# Nevron_v4.net
KiCad netlist of a schematic drawn in Altium Designer
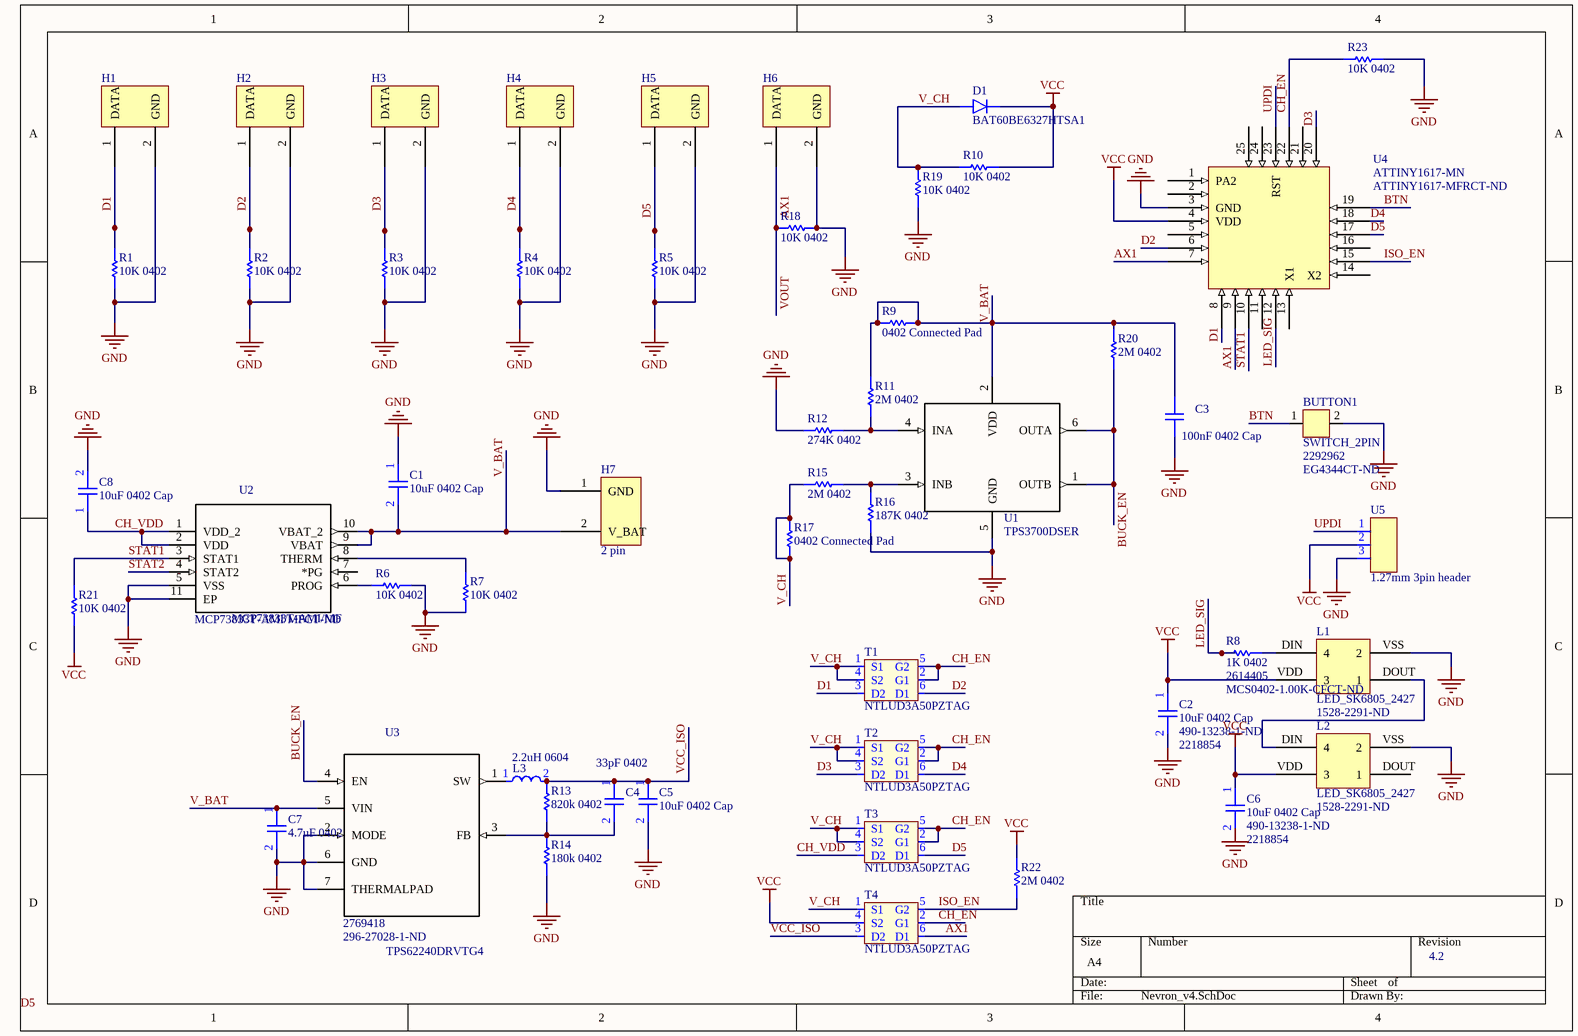
[diagram p0: Nevron_v4.SchDoc]

(export (version "E")
  (design (tool "Eeschema 10.0.6"))
  (components
    (comp (ref "BUTTON1")
      (value "SWITCH_2PIN")
      (footprint "SWITCH- TL1015AF160QG")
      (fields
        (field (name "SUPPLIER PART NUMBER 1") "2292962")
        (field (name "SUPPLIER PART NUMBER 2") "EG4344CT-ND")
      )
      (libsource (lib "Nevron_v4") (part "SWITCH_2PIN"))
    )
    (comp (ref "C1")
      (value "10uF 0402 Cap")
      (footprint "0402 Cap")
      (libsource (lib "Nevron_v4") (part "10uF 0402 Cap"))
    )
    (comp (ref "C2")
      (value "10uF 0402 Cap")
      (footprint "0402 Cap")
      (fields
        (field (name "SUPPLIER PART NUMBER 1") "490-13238-1-ND")
        (field (name "SUPPLIER PART NUMBER 2") "2218854")
      )
      (libsource (lib "Nevron_v4") (part "10uF 0402 Cap"))
    )
    (comp (ref "C3")
      (value "100nF 0402 Cap")
      (footprint "0402 Cap")
      (libsource (lib "Nevron_v4") (part "100nF 0402 Cap"))
    )
    (comp (ref "C4")
      (value "33pF 0402")
      (footprint "0402 Cap")
      (libsource (lib "Nevron_v4") (part "33pF 0402"))
    )
    (comp (ref "C5")
      (value "10uF 0402 Cap")
      (footprint "0402 Cap")
      (libsource (lib "Nevron_v4") (part "10uF 0402 Cap"))
    )
    (comp (ref "C6")
      (value "10uF 0402 Cap")
      (footprint "0402 Cap")
      (fields
        (field (name "SUPPLIER PART NUMBER 1") "490-13238-1-ND")
        (field (name "SUPPLIER PART NUMBER 2") "2218854")
      )
      (libsource (lib "Nevron_v4") (part "10uF 0402 Cap"))
    )
    (comp (ref "C7")
      (value "4.7uF 0402")
      (footprint "0402 Cap")
      (libsource (lib "Nevron_v4") (part "4.7uF 0402"))
    )
    (comp (ref "C8")
      (value "10uF 0402 Cap")
      (footprint "0402 Cap")
      (libsource (lib "Nevron_v4") (part "10uF 0402 Cap"))
    )
    (comp (ref "D1")
      (value "BAT60BE6327HTSA1")
      (footprint "BAT60BE6327HTSA1")
      (description "Diode Schottky 10V 3A Automotive 2-Pin SOD-323 T/R")
      (fields (field (name "MANUFACTURER") "Infineon"))
      (libsource (lib "Nevron_v4") (part "BAT60BE6327HTSA1"))
    )
    (comp (ref "H1")
      (value "Magnetci con. 2 pin")
      (footprint "Magnetic con. 2 pin")
      (libsource (lib "Nevron_v4") (part "Magnetci con. 2 pin"))
    )
    (comp (ref "H2")
      (value "Magnetci con. 2 pin")
      (footprint "Magnetic con. 2 pin")
      (libsource (lib "Nevron_v4") (part "Magnetci con. 2 pin"))
    )
    (comp (ref "H3")
      (value "Magnetci con. 2 pin")
      (footprint "Magnetic con. 2 pin")
      (libsource (lib "Nevron_v4") (part "Magnetci con. 2 pin"))
    )
    (comp (ref "H4")
      (value "Magnetci con. 2 pin")
      (footprint "Magnetic con. 2 pin")
      (libsource (lib "Nevron_v4") (part "Magnetci con. 2 pin"))
    )
    (comp (ref "H5")
      (value "Magnetci con. 2 pin")
      (footprint "Magnetic con. 2 pin")
      (libsource (lib "Nevron_v4") (part "Magnetci con. 2 pin"))
    )
    (comp (ref "H6")
      (value "Magnetci con. 2 pin")
      (footprint "Magnetic con. 2 pin")
      (libsource (lib "Nevron_v4") (part "Magnetci con. 2 pin"))
    )
    (comp (ref "H7") (value "2 pin") (footprint "2_PIN") (libsource (lib "Nevron_v1") (part "2 pin")))
    (comp (ref "L1")
      (value "LED_SK6805_2427")
      (footprint "LED_SK6805_2427")
      (fields (field (name "SUPPLIER PART NUMBER 1") "1528-2291-ND"))
      (libsource (lib "Nevron_v4") (part "LED_SK6805_2427"))
    )
    (comp (ref "L2")
      (value "LED_SK6805_2427")
      (footprint "LED_SK6805_2427")
      (fields (field (name "SUPPLIER PART NUMBER 1") "1528-2291-ND"))
      (libsource (lib "Nevron_v4") (part "LED_SK6805_2427"))
    )
    (comp (ref "L3")
      (value "2.2uH 0604")
      (footprint "0603 inductor")
      (libsource (lib "Nevron_v4") (part "2.2uH 0604"))
    )
    (comp (ref "R1")
      (value "10K 0402")
      (footprint "0402 Res")
      (libsource (lib "Nevron_v4") (part "10K 0402"))
    )
    (comp (ref "R2")
      (value "10K 0402")
      (footprint "0402 Res")
      (libsource (lib "Nevron_v4") (part "10K 0402"))
    )
    (comp (ref "R3")
      (value "10K 0402")
      (footprint "0402 Res")
      (libsource (lib "Nevron_v4") (part "10K 0402"))
    )
    (comp (ref "R4")
      (value "10K 0402")
      (footprint "0402 Res")
      (libsource (lib "Nevron_v4") (part "10K 0402"))
    )
    (comp (ref "R5")
      (value "10K 0402")
      (footprint "0402 Res")
      (libsource (lib "Nevron_v4") (part "10K 0402"))
    )
    (comp (ref "R6")
      (value "10K 0402")
      (footprint "0402 Res")
      (libsource (lib "Nevron_v4") (part "10K 0402"))
    )
    (comp (ref "R7")
      (value "10K 0402")
      (footprint "0402 Res")
      (libsource (lib "Nevron_v4") (part "10K 0402"))
    )
    (comp (ref "R8")
      (value "1K 0402")
      (footprint "0402 Res")
      (fields
        (field (name "SUPPLIER PART NUMBER 1") "2614405")
        (field (name "SUPPLIER PART NUMBER 2") "MCS0402-1.00K-CFCT-ND")
      )
      (libsource (lib "Nevron_v4") (part "1K 0402"))
    )
    (comp (ref "R9")
      (value "0402 Connected Pad")
      (footprint "0402 connected pad")
      (libsource (lib "Nevron_v4") (part "0402 Connected Pad"))
    )
    (comp (ref "R10")
      (value "10K 0402")
      (footprint "0402 Res")
      (libsource (lib "Nevron_v4") (part "10K 0402"))
    )
    (comp (ref "R11")
      (value "2M 0402")
      (footprint "0402 Res")
      (description "RES SMD 2M OHM 1% 1/16W 0402")
      (fields
        (field (name "MANUFACTURER") "Vishay Dale")
        (field (name "MANUFACTURER PART NUMBER") "CRCW04021M00DHEDP")
      )
      (libsource (lib "Nevron_v4") (part "2M 0402"))
    )
    (comp (ref "R12")
      (value "274K 0402")
      (footprint "0402 Res")
      (libsource (lib "Nevron_v4") (part "274K 0402"))
    )
    (comp (ref "R13")
      (value "820k 0402")
      (footprint "0402 Res")
      (libsource (lib "Nevron_v4") (part "820k 0402"))
    )
    (comp (ref "R14")
      (value "180k 0402")
      (footprint "0402 Res")
      (libsource (lib "Nevron_v4") (part "180k 0402"))
    )
    (comp (ref "R15")
      (value "2M 0402")
      (footprint "0402 Res")
      (description "RES SMD 2M OHM 1% 1/16W 0402")
      (fields
        (field (name "MANUFACTURER") "Vishay Dale")
        (field (name "MANUFACTURER PART NUMBER") "CRCW04021M00DHEDP")
      )
      (libsource (lib "Nevron_v4") (part "2M 0402"))
    )
    (comp (ref "R16")
      (value "187K 0402")
      (footprint "0402 Res")
      (libsource (lib "Nevron_v4") (part "187K 0402"))
    )
    (comp (ref "R17")
      (value "0402 Connected Pad")
      (footprint "0402 connected pad")
      (libsource (lib "Nevron_v4") (part "0402 Connected Pad"))
    )
    (comp (ref "R18")
      (value "10K 0402")
      (footprint "0402 Res")
      (libsource (lib "Nevron_v4") (part "10K 0402"))
    )
    (comp (ref "R19")
      (value "10K 0402")
      (footprint "0402 Res")
      (libsource (lib "Nevron_v4") (part "10K 0402"))
    )
    (comp (ref "R20")
      (value "2M 0402")
      (footprint "0402 Res")
      (description "RES SMD 2M OHM 1% 1/16W 0402")
      (fields
        (field (name "MANUFACTURER") "Vishay Dale")
        (field (name "MANUFACTURER PART NUMBER") "CRCW04021M00DHEDP")
      )
      (libsource (lib "Nevron_v4") (part "2M 0402"))
    )
    (comp (ref "R21")
      (value "10K 0402")
      (footprint "0402 Res")
      (libsource (lib "Nevron_v4") (part "10K 0402"))
    )
    (comp (ref "R22")
      (value "2M 0402")
      (footprint "0402 Res")
      (description "RES SMD 2M OHM 1% 1/16W 0402")
      (fields
        (field (name "MANUFACTURER") "Vishay Dale")
        (field (name "MANUFACTURER PART NUMBER") "CRCW04021M00DHEDP")
      )
      (libsource (lib "Nevron_v4") (part "2M 0402"))
    )
    (comp (ref "R23")
      (value "10K 0402")
      (footprint "0402 Res")
      (libsource (lib "Nevron_v4") (part "10K 0402"))
    )
    (comp (ref "T1")
      (value "NTLUD3A50PZTAG")
      (footprint "NTLUD3A50PZTAG")
      (libsource (lib "Nevron_v4") (part "NTLUD3A50PZTAG"))
    )
    (comp (ref "T2")
      (value "NTLUD3A50PZTAG")
      (footprint "NTLUD3A50PZTAG")
      (libsource (lib "Nevron_v4") (part "NTLUD3A50PZTAG"))
    )
    (comp (ref "T3")
      (value "NTLUD3A50PZTAG")
      (footprint "NTLUD3A50PZTAG")
      (libsource (lib "Nevron_v4") (part "NTLUD3A50PZTAG"))
    )
    (comp (ref "T4")
      (value "NTLUD3A50PZTAG")
      (footprint "NTLUD3A50PZTAG")
      (libsource (lib "Nevron_v4") (part "NTLUD3A50PZTAG"))
    )
    (comp (ref "U1")
      (value "TPS3700DSER")
      (footprint "TPS3700DSER")
      (description "IC COMPARATOR WINDOW")
      (fields (field (name "MANUFACTURER") "Texas Instruments"))
      (libsource (lib "Nevron_v4") (part "TPS3700DSER"))
    )
    (comp (ref "U2")
      (value "MCP73833T-AMI/MF")
      (footprint "MCP73833T-AMI/MF")
      (description "Linear Charge Management Controller Li-Ion/Li-Pol 1mA 4.2V/4.35V/4.4V/4.5V 10-Pin DFN EP T/R")
      (fields
        (field (name "MP") "MCP73833-AMI/UN")
        (field (name "MF") "Microchip")
        (field (name "SUPPLIER PART NUMBER 1") "MCP73833T-AMI/MFCT-ND")
      )
      (libsource (lib "Nevron_v4") (part "MCP73833T-AMI/MF"))
    )
    (comp (ref "U3")
      (value "TPS62240DRVTG4")
      (footprint "TPS62240DRVR")
      (description "Conv DC-DC 2V to 6V Synchronous Step Down Single-Out 0.6V to 6V 0.3A 6-Pin WSON EP T/R")
      (fields
        (field (name "MF") "Texas Instruments")
        (field (name "SUPPLIER PART NUMBER 1") "2769418")
        (field (name "SUPPLIER PART NUMBER 2") "296-27028-1-ND")
      )
      (libsource (lib "Nevron_v4") (part "TPS62240DRVR"))
    )
    (comp (ref "U4")
      (value "ATTINY1617-MN")
      (footprint "ATtiny1617_QFN50P400X400X90_HS-25M")
      (fields (field (name "SUPPLIER PART NUMBER 1") "ATTINY1617-MFRCT-ND"))
      (libsource (lib "Nevron_v4") (part "ATTINY1617-MN"))
    )
    (comp (ref "U5")
      (value "1.27mm 3pin header")
      (footprint "1.27mm 3pin header")
      (libsource (lib "Nevron_v4") (part "1.27mm 3pin header"))
    )
  )
  (nets
    (net (code "1") (name "/AX1") (class "Default")
      (node (ref "H6") (pin "1") (pinfunction "DATA_1") (pintype "passive"))
      (node (ref "R18") (pin "1") (pintype "passive"))
      (node (ref "T4") (pin "6") (pinfunction "D1_6") (pintype "passive"))
      (node (ref "U4") (pin "7") (pintype "input"))
      (node (ref "U4") (pin "9") (pintype "input"))
    )
    (net (code "2") (name "/BTN") (class "Default")
      (node (ref "BUTTON1") (pin "1") (pintype "passive"))
      (node (ref "U4") (pin "19") (pintype "input"))
    )
    (net (code "3") (name "/BUCK_EN") (class "Default")
      (node (ref "R20") (pin "2") (pintype "passive"))
      (node (ref "U1") (pin "1") (pinfunction "OUTB_1") (pintype "output"))
      (node (ref "U1") (pin "6") (pinfunction "OUTA_6") (pintype "output"))
      (node (ref "U3") (pin "4") (pinfunction "EN_4") (pintype "input"))
    )
    (net (code "4") (name "/CH_EN") (class "Default")
      (node (ref "R23") (pin "1") (pintype "passive"))
      (node (ref "T1") (pin "2") (pinfunction "G1_2") (pintype "passive"))
      (node (ref "T1") (pin "5") (pinfunction "G2_5") (pintype "passive"))
      (node (ref "T2") (pin "2") (pinfunction "G1_2") (pintype "passive"))
      (node (ref "T2") (pin "5") (pinfunction "G2_5") (pintype "passive"))
      (node (ref "T3") (pin "2") (pinfunction "G1_2") (pintype "passive"))
      (node (ref "T3") (pin "5") (pinfunction "G2_5") (pintype "passive"))
      (node (ref "T4") (pin "2") (pinfunction "G1_2") (pintype "passive"))
      (node (ref "U4") (pin "22") (pintype "input"))
    )
    (net (code "5") (name "/CH_VDD") (class "Default")
      (node (ref "C8") (pin "1") (pintype "passive"))
      (node (ref "T3") (pin "3") (pinfunction "D2_3") (pintype "passive"))
      (node (ref "U2") (pin "1") (pinfunction "VDD_2_1") (pintype "power_in"))
      (node (ref "U2") (pin "2") (pinfunction "VDD_2") (pintype "power_in"))
    )
    (net (code "6") (name "/D1") (class "Default")
      (node (ref "H1") (pin "1") (pinfunction "DATA_1") (pintype "passive"))
      (node (ref "R1") (pin "1") (pintype "passive"))
      (node (ref "T1") (pin "3") (pinfunction "D2_3") (pintype "passive"))
      (node (ref "U4") (pin "8") (pintype "input"))
    )
    (net (code "7") (name "/D2") (class "Default")
      (node (ref "H2") (pin "1") (pinfunction "DATA_1") (pintype "passive"))
      (node (ref "R2") (pin "1") (pintype "passive"))
      (node (ref "T1") (pin "6") (pinfunction "D1_6") (pintype "passive"))
      (node (ref "U4") (pin "6") (pintype "input"))
    )
    (net (code "8") (name "/D3") (class "Default")
      (node (ref "H3") (pin "1") (pinfunction "DATA_1") (pintype "passive"))
      (node (ref "R3") (pin "1") (pintype "passive"))
      (node (ref "T2") (pin "3") (pinfunction "D2_3") (pintype "passive"))
      (node (ref "U4") (pin "20") (pintype "input"))
    )
    (net (code "9") (name "/D4") (class "Default")
      (node (ref "H4") (pin "1") (pinfunction "DATA_1") (pintype "passive"))
      (node (ref "R4") (pin "1") (pintype "passive"))
      (node (ref "T2") (pin "6") (pinfunction "D1_6") (pintype "passive"))
      (node (ref "U4") (pin "18") (pintype "input"))
    )
    (net (code "10") (name "/D5") (class "Default")
      (node (ref "H5") (pin "1") (pinfunction "DATA_1") (pintype "passive"))
      (node (ref "R5") (pin "1") (pintype "passive"))
      (node (ref "T3") (pin "6") (pinfunction "D1_6") (pintype "passive"))
      (node (ref "U4") (pin "17") (pintype "input"))
    )
    (net (code "11") (name "/ISO_EN") (class "Default")
      (node (ref "R22") (pin "2") (pintype "passive"))
      (node (ref "T4") (pin "5") (pinfunction "G2_5") (pintype "passive"))
      (node (ref "U4") (pin "15") (pintype "input"))
    )
    (net (code "12") (name "/LED_SIG") (class "Default")
      (node (ref "R8") (pin "1") (pintype "passive"))
      (node (ref "U4") (pin "12") (pintype "input"))
    )
    (net (code "13") (name "/STAT1") (class "Default")
      (node (ref "R21") (pin "1") (pintype "passive"))
      (node (ref "U2") (pin "3") (pinfunction "STAT1_3") (pintype "input"))
      (node (ref "U4") (pin "10") (pintype "input"))
    )
    (net (code "14") (name "/STAT2") (class "Default")
      (node (ref "U2") (pin "4") (pinfunction "STAT2_4") (pintype "input"))
    )
    (net (code "15") (name "/UPDI") (class "Default")
      (node (ref "U4") (pin "23") (pinfunction "RST_23") (pintype "input"))
      (node (ref "U5") (pin "1") (pintype "passive"))
    )
    (net (code "16") (name "/VCC_ISO") (class "Default")
      (node (ref "C4") (pin "1") (pintype "passive"))
      (node (ref "C5") (pin "1") (pintype "passive"))
      (node (ref "L3") (pin "2") (pintype "passive"))
      (node (ref "R13") (pin "1") (pintype "passive"))
      (node (ref "T4") (pin "3") (pinfunction "D2_3") (pintype "passive"))
    )
    (net (code "17") (name "/V_BAT") (class "Default")
      (node (ref "C1") (pin "2") (pintype "passive"))
      (node (ref "C3") (pin "1") (pintype "passive"))
      (node (ref "C7") (pin "1") (pintype "passive"))
      (node (ref "H7") (pin "2") (pinfunction "V_BAT_2") (pintype "passive"))
      (node (ref "R11") (pin "1") (pintype "passive"))
      (node (ref "R20") (pin "1") (pintype "passive"))
      (node (ref "R9") (pin "1") (pintype "passive"))
      (node (ref "R9") (pin "2") (pintype "passive"))
      (node (ref "U1") (pin "2") (pinfunction "VDD_2") (pintype "power_in"))
      (node (ref "U2") (pin "10") (pinfunction "VBAT_2_10") (pintype "output"))
      (node (ref "U2") (pin "9") (pinfunction "VBAT_9") (pintype "output"))
      (node (ref "U3") (pin "5") (pinfunction "VIN_5") (pintype "power_in"))
    )
    (net (code "18") (name "/V_CH") (class "Default")
      (node (ref "D1") (pin "A") (pintype "passive"))
      (node (ref "R10") (pin "1") (pintype "passive"))
      (node (ref "R15") (pin "1") (pintype "passive"))
      (node (ref "R17") (pin "1") (pintype "passive"))
      (node (ref "R17") (pin "2") (pintype "passive"))
      (node (ref "R19") (pin "1") (pintype "passive"))
      (node (ref "T1") (pin "1") (pinfunction "S1_1") (pintype "passive"))
      (node (ref "T1") (pin "4") (pinfunction "S2_4") (pintype "passive"))
      (node (ref "T2") (pin "1") (pinfunction "S1_1") (pintype "passive"))
      (node (ref "T2") (pin "4") (pinfunction "S2_4") (pintype "passive"))
      (node (ref "T3") (pin "1") (pinfunction "S1_1") (pintype "passive"))
      (node (ref "T3") (pin "4") (pinfunction "S2_4") (pintype "passive"))
      (node (ref "T4") (pin "1") (pinfunction "S1_1") (pintype "passive"))
    )
    (net (code "19") (name "GND") (class "Default")
      (node (ref "BUTTON1") (pin "2") (pintype "passive"))
      (node (ref "C1") (pin "1") (pintype "passive"))
      (node (ref "C2") (pin "2") (pintype "passive"))
      (node (ref "C3") (pin "2") (pintype "passive"))
      (node (ref "C5") (pin "2") (pintype "passive"))
      (node (ref "C6") (pin "2") (pintype "passive"))
      (node (ref "C7") (pin "2") (pintype "passive"))
      (node (ref "C8") (pin "2") (pintype "passive"))
      (node (ref "H1") (pin "2") (pinfunction "GND_2") (pintype "passive"))
      (node (ref "H2") (pin "2") (pinfunction "GND_2") (pintype "passive"))
      (node (ref "H3") (pin "2") (pinfunction "GND_2") (pintype "passive"))
      (node (ref "H4") (pin "2") (pinfunction "GND_2") (pintype "passive"))
      (node (ref "H5") (pin "2") (pinfunction "GND_2") (pintype "passive"))
      (node (ref "H6") (pin "2") (pinfunction "GND_2") (pintype "passive"))
      (node (ref "H7") (pin "1") (pinfunction "GND_1") (pintype "passive"))
      (node (ref "L1") (pin "VSS") (pinfunction "2_VSS") (pintype "passive"))
      (node (ref "L2") (pin "VSS") (pinfunction "2_VSS") (pintype "passive"))
      (node (ref "R1") (pin "2") (pintype "passive"))
      (node (ref "R12") (pin "1") (pintype "passive"))
      (node (ref "R14") (pin "2") (pintype "passive"))
      (node (ref "R16") (pin "2") (pintype "passive"))
      (node (ref "R18") (pin "2") (pintype "passive"))
      (node (ref "R19") (pin "2") (pintype "passive"))
      (node (ref "R2") (pin "2") (pintype "passive"))
      (node (ref "R23") (pin "2") (pintype "passive"))
      (node (ref "R3") (pin "2") (pintype "passive"))
      (node (ref "R4") (pin "2") (pintype "passive"))
      (node (ref "R5") (pin "2") (pintype "passive"))
      (node (ref "R6") (pin "2") (pintype "passive"))
      (node (ref "R7") (pin "2") (pintype "passive"))
      (node (ref "U1") (pin "5") (pinfunction "GND_5") (pintype "passive"))
      (node (ref "U2") (pin "11") (pinfunction "EP_11") (pintype "passive"))
      (node (ref "U2") (pin "5") (pinfunction "VSS_5") (pintype "passive"))
      (node (ref "U3") (pin "2") (pinfunction "MODE_2") (pintype "input"))
      (node (ref "U3") (pin "6") (pinfunction "GND_6") (pintype "passive"))
      (node (ref "U3") (pin "7") (pinfunction "THERMALPAD_7") (pintype "passive"))
      (node (ref "U4") (pin "3") (pinfunction "GND_3") (pintype "input"))
      (node (ref "U5") (pin "3") (pintype "passive"))
    )
    (net (code "20") (name "Net-(L1-1)") (class "Default")
      (node (ref "L1") (pin "DOUT") (pinfunction "1_DOUT") (pintype "passive"))
      (node (ref "L2") (pin "DIN") (pinfunction "4_DIN") (pintype "passive"))
    )
    (net (code "21") (name "Net-(L1-4)") (class "Default")
      (node (ref "L1") (pin "DIN") (pinfunction "4_DIN") (pintype "passive"))
      (node (ref "R8") (pin "2") (pintype "passive"))
    )
    (net (code "22") (name "Net-(U1-INA)") (class "Default")
      (node (ref "R11") (pin "2") (pintype "passive"))
      (node (ref "R12") (pin "2") (pintype "passive"))
      (node (ref "U1") (pin "4") (pinfunction "INA_4") (pintype "input"))
    )
    (net (code "23") (name "Net-(U1-INB)") (class "Default")
      (node (ref "R15") (pin "2") (pintype "passive"))
      (node (ref "R16") (pin "1") (pintype "passive"))
      (node (ref "U1") (pin "3") (pinfunction "INB_3") (pintype "input"))
    )
    (net (code "24") (name "Net-(U2-PROG)") (class "Default")
      (node (ref "R6") (pin "1") (pintype "passive"))
      (node (ref "U2") (pin "6") (pinfunction "PROG_6") (pintype "input"))
    )
    (net (code "25") (name "Net-(U2-THERM)") (class "Default")
      (node (ref "R7") (pin "1") (pintype "passive"))
      (node (ref "U2") (pin "8") (pinfunction "THERM_8") (pintype "input"))
    )
    (net (code "26") (name "Net-(U3-FB)") (class "Default")
      (node (ref "C4") (pin "2") (pintype "passive"))
      (node (ref "R13") (pin "2") (pintype "passive"))
      (node (ref "R14") (pin "1") (pintype "passive"))
      (node (ref "U3") (pin "3") (pinfunction "FB_3") (pintype "input"))
    )
    (net (code "27") (name "Net-(U3-SW)") (class "Default")
      (node (ref "L3") (pin "1") (pintype "passive"))
      (node (ref "U3") (pin "1") (pinfunction "SW_1") (pintype "output"))
    )
    (net (code "28") (name "VCC") (class "Default")
      (node (ref "C2") (pin "1") (pintype "passive"))
      (node (ref "C6") (pin "1") (pintype "passive"))
      (node (ref "D1") (pin "K") (pintype "passive"))
      (node (ref "L1") (pin "VDD") (pinfunction "3_VDD") (pintype "passive"))
      (node (ref "L2") (pin "VDD") (pinfunction "3_VDD") (pintype "passive"))
      (node (ref "R10") (pin "2") (pintype "passive"))
      (node (ref "R21") (pin "2") (pintype "passive"))
      (node (ref "R22") (pin "1") (pintype "passive"))
      (node (ref "T4") (pin "4") (pinfunction "S2_4") (pintype "passive"))
      (node (ref "U4") (pin "4") (pinfunction "VDD_4") (pintype "input"))
      (node (ref "U5") (pin "2") (pintype "passive"))
    )
    (net (code "29") (name "unconnected-(L2-1-PadDOUT)") (class "Default")
      (node (ref "L2") (pin "DOUT") (pinfunction "1_DOUT") (pintype "passive"))
    )
    (net (code "30") (name "unconnected-(U2-*PG-Pad7)") (class "Default")
      (node (ref "U2") (pin "7") (pinfunction "*PG_7") (pintype "input"))
    )
    (net (code "31") (name "unconnected-(U4-PA2-Pad1)") (class "Default")
      (node (ref "U4") (pin "1") (pinfunction "PA2_1") (pintype "input"))
    )
    (net (code "32") (name "unconnected-(U4-Pad2)") (class "Default")
      (node (ref "U4") (pin "2") (pintype "input"))
    )
    (net (code "33") (name "unconnected-(U4-Pad5)") (class "Default")
      (node (ref "U4") (pin "5") (pintype "input"))
    )
    (net (code "34") (name "unconnected-(U4-Pad11)") (class "Default")
      (node (ref "U4") (pin "11") (pintype "input"))
    )
    (net (code "35") (name "unconnected-(U4-Pad16)") (class "Default")
      (node (ref "U4") (pin "16") (pintype "input"))
    )
    (net (code "36") (name "unconnected-(U4-Pad21)") (class "Default")
      (node (ref "U4") (pin "21") (pintype "input"))
    )
    (net (code "37") (name "unconnected-(U4-Pad24)") (class "Default")
      (node (ref "U4") (pin "24") (pintype "input"))
    )
    (net (code "38") (name "unconnected-(U4-Pad25)") (class "Default")
      (node (ref "U4") (pin "25") (pintype "input"))
    )
    (net (code "39") (name "unconnected-(U4-X1-Pad13)") (class "Default")
      (node (ref "U4") (pin "13") (pinfunction "X1_13") (pintype "input"))
    )
    (net (code "40") (name "unconnected-(U4-X2-Pad14)") (class "Default")
      (node (ref "U4") (pin "14") (pinfunction "X2_14") (pintype "input"))
    )
  )
)
